# Power-up_delay.net
KiCad netlist of a schematic drawn in Altium Designer
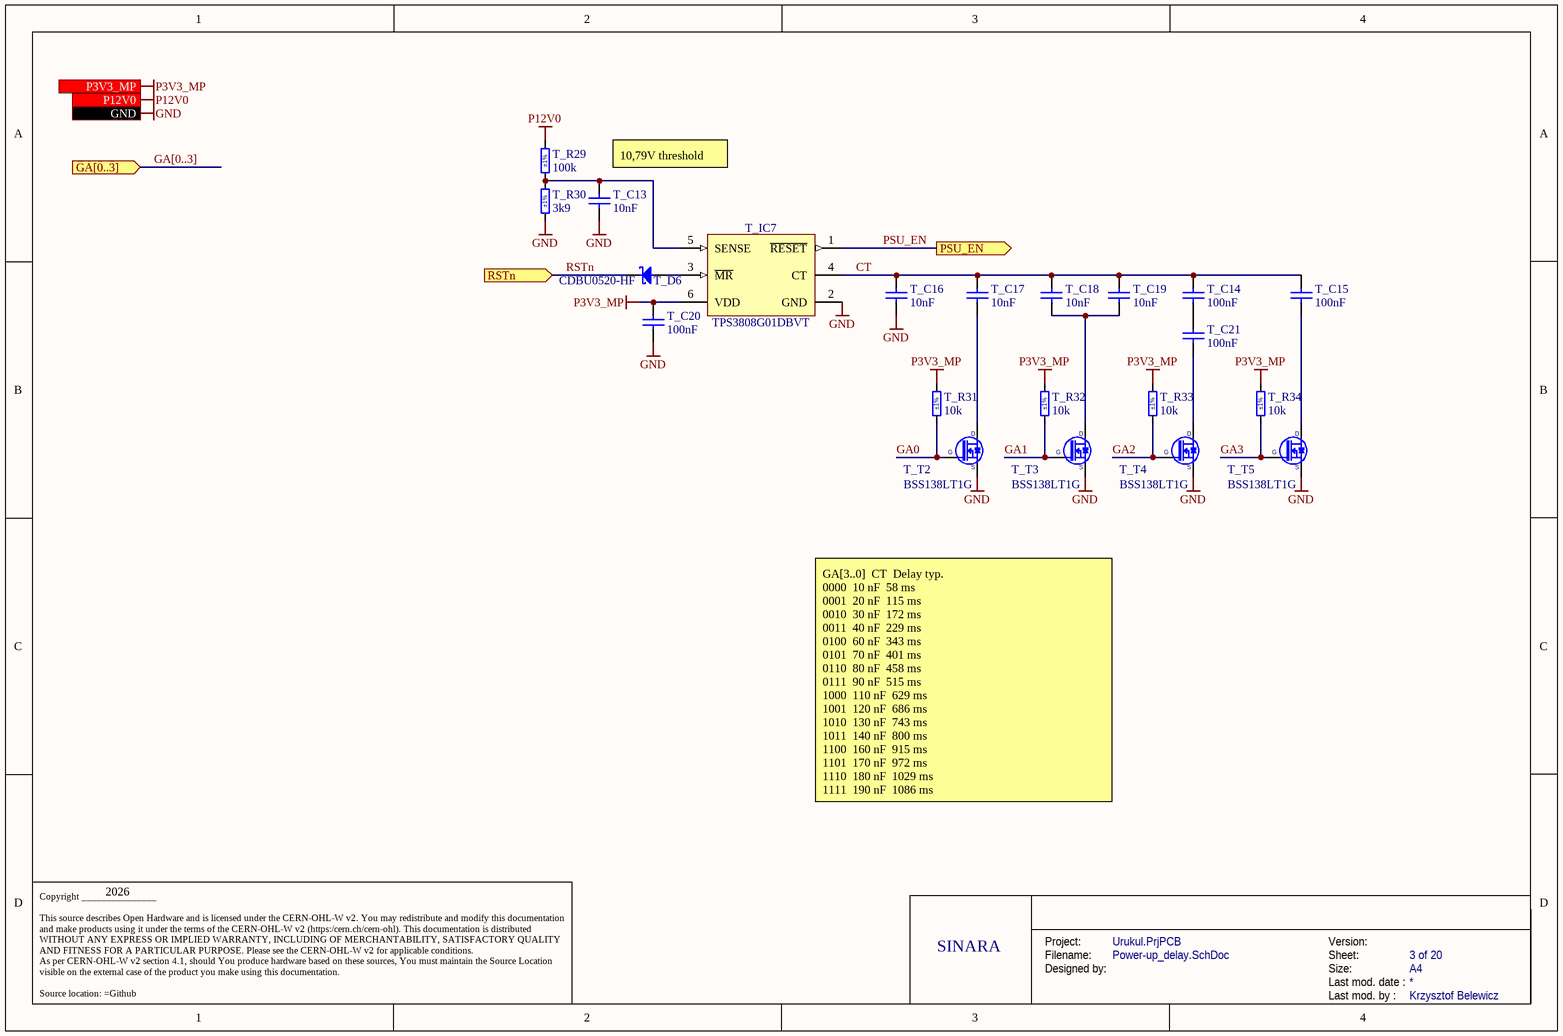
[diagram p0: Power-up_delay.SchDoc]

(export (version "E")
  (design (tool "Eeschema 10.0.6"))
  (components
    (comp (ref "T_C13")
      (value "10nF")
      (footprint "CAPC1005X55N")
      (description "Non-polarised capacitor")
      (fields
        (field (name "PART NUMBER") "CC0402_10NF_16V_10%_X7R")
        (field (name "VOLTAGE") "16V")
        (field (name "AUTHOR") "CERN DEM JLC")
      )
      (libsource (lib "Capacitors") (part "Capacitor - non polarized"))
    )
    (comp (ref "T_C14")
      (value "100nF")
      (footprint "CAPC1005X55N")
      (description "Non-polarised capacitor")
      (fields
        (field (name "PART NUMBER") "CC0402_100NF_16V_10%_X5R")
        (field (name "VOLTAGE") "16V")
        (field (name "AUTHOR") "CERN DEM JLC")
      )
      (libsource (lib "Capacitors") (part "Capacitor - non polarized"))
    )
    (comp (ref "T_C15")
      (value "100nF")
      (footprint "CAPC1005X55N")
      (description "Non-polarised capacitor")
      (fields
        (field (name "PART NUMBER") "CC0402_100NF_16V_10%_X5R")
        (field (name "VOLTAGE") "16V")
        (field (name "AUTHOR") "CERN DEM JLC")
      )
      (libsource (lib "Capacitors") (part "Capacitor - non polarized"))
    )
    (comp (ref "T_C16")
      (value "10nF")
      (footprint "CAPC1005X55N")
      (description "Non-polarised capacitor")
      (fields
        (field (name "PART NUMBER") "CC0402_10NF_16V_10%_X7R")
        (field (name "VOLTAGE") "16V")
        (field (name "AUTHOR") "CERN DEM JLC")
      )
      (libsource (lib "Capacitors") (part "Capacitor - non polarized"))
    )
    (comp (ref "T_C17")
      (value "10nF")
      (footprint "CAPC1005X55N")
      (description "Non-polarised capacitor")
      (fields
        (field (name "PART NUMBER") "CC0402_10NF_16V_10%_X7R")
        (field (name "VOLTAGE") "16V")
        (field (name "AUTHOR") "CERN DEM JLC")
      )
      (libsource (lib "Capacitors") (part "Capacitor - non polarized"))
    )
    (comp (ref "T_C18")
      (value "10nF")
      (footprint "CAPC1005X55N")
      (description "Non-polarised capacitor")
      (fields
        (field (name "PART NUMBER") "CC0402_10NF_16V_10%_X7R")
        (field (name "VOLTAGE") "16V")
        (field (name "AUTHOR") "CERN DEM JLC")
      )
      (libsource (lib "Capacitors") (part "Capacitor - non polarized"))
    )
    (comp (ref "T_C19")
      (value "10nF")
      (footprint "CAPC1005X55N")
      (description "Non-polarised capacitor")
      (fields
        (field (name "PART NUMBER") "CC0402_10NF_16V_10%_X7R")
        (field (name "VOLTAGE") "16V")
        (field (name "AUTHOR") "CERN DEM JLC")
      )
      (libsource (lib "Capacitors") (part "Capacitor - non polarized"))
    )
    (comp (ref "T_C20")
      (value "100nF")
      (footprint "CAPC1005X55N")
      (description "Non-polarised capacitor")
      (fields
        (field (name "PART NUMBER") "CC0402_100NF_16V_10%_X5R")
        (field (name "VOLTAGE") "16V")
        (field (name "AUTHOR") "CERN DEM JLC")
      )
      (libsource (lib "Capacitors") (part "Capacitor - non polarized"))
    )
    (comp (ref "T_C21")
      (value "100nF")
      (footprint "CAPC1005X55N")
      (description "Non-polarised capacitor")
      (fields
        (field (name "PART NUMBER") "CC0402_100NF_16V_10%_X5R")
        (field (name "VOLTAGE") "16V")
        (field (name "AUTHOR") "CERN DEM JLC")
      )
      (libsource (lib "Capacitors") (part "Capacitor - non polarized"))
    )
    (comp (ref "T_D6")
      (value "CDBU0520-HF")
      (footprint "SOD-523F")
      (description "Schottky Diode")
      (fields
        (field (name "VOLTAGE") "20V")
        (field (name "POWER") "500mA")
        (field (name "AUTHOR") "CERN DEM HF")
      )
      (libsource (lib "ICs And Semiconductors") (part "Diode Schottky"))
    )
    (comp (ref "T_IC7")
      (value "TPS3808G01DBVT")
      (footprint "SOT95P280X145-6N")
      (description "Low Quiescent Current, Programmable-Delay Supervisory Circuit")
      (fields
        (field (name "MANUFACTURER") "TEXAS INSTRUMENTS")
        (field (name "MANUFACTURER PART NUMBER") "TPS3808G01DBV")
        (field (name "AUTHOR") "CERN DEM JLC")
      )
      (libsource (lib "ICs And Semiconductors") (part "TPS3808xxxDBV"))
    )
    (comp (ref "T_R29")
      (value "100k")
      (footprint "RESC1005X40N")
      (description "Resistor - 1%")
      (fields
        (field (name "TOLERANCE") "±1%")
        (field (name "PART NUMBER") "R0402_100K_1%_0.0625W_100PPM")
        (field (name "POWER") "0.0625W")
        (field (name "AUTHOR") "CERN DEM JLC")
      )
      (libsource (lib "Resistors") (part "Resistor - 1%"))
    )
    (comp (ref "T_R30")
      (value "3k9")
      (footprint "RESC1005X40N")
      (description "Resistor - 1%")
      (fields
        (field (name "TOLERANCE") "±1%")
        (field (name "PART NUMBER") "R0402_3K9_1%_0.0625W_100PPM")
        (field (name "POWER") "0.0625W")
        (field (name "AUTHOR") "CERN DEM JLC")
      )
      (libsource (lib "Resistors") (part "Resistor - 1%"))
    )
    (comp (ref "T_R31")
      (value "10k")
      (footprint "RESC1005X40N")
      (description "Resistor - 1%")
      (fields
        (field (name "TOLERANCE") "±1%")
        (field (name "PART NUMBER") "R0402_10K_1%_0.0625W_100PPM")
        (field (name "POWER") "0.0625W")
        (field (name "AUTHOR") "CERN DEM JLC")
      )
      (libsource (lib "Resistors") (part "Resistor - 1%"))
    )
    (comp (ref "T_R32")
      (value "10k")
      (footprint "RESC1005X40N")
      (description "Resistor - 1%")
      (fields
        (field (name "TOLERANCE") "±1%")
        (field (name "PART NUMBER") "R0402_10K_1%_0.0625W_100PPM")
        (field (name "POWER") "0.0625W")
        (field (name "AUTHOR") "CERN DEM JLC")
      )
      (libsource (lib "Resistors") (part "Resistor - 1%"))
    )
    (comp (ref "T_R33")
      (value "10k")
      (footprint "RESC1005X40N")
      (description "Resistor - 1%")
      (fields
        (field (name "TOLERANCE") "±1%")
        (field (name "PART NUMBER") "R0402_10K_1%_0.0625W_100PPM")
        (field (name "POWER") "0.0625W")
        (field (name "AUTHOR") "CERN DEM JLC")
      )
      (libsource (lib "Resistors") (part "Resistor - 1%"))
    )
    (comp (ref "T_R34")
      (value "10k")
      (footprint "RESC1005X40N")
      (description "Resistor - 1%")
      (fields
        (field (name "TOLERANCE") "±1%")
        (field (name "PART NUMBER") "R0402_10K_1%_0.0625W_100PPM")
        (field (name "POWER") "0.0625W")
        (field (name "AUTHOR") "CERN DEM JLC")
      )
      (libsource (lib "Resistors") (part "Resistor - 1%"))
    )
    (comp (ref "T_T2")
      (value "BSS138LT1G")
      (footprint "SOT95P240X110-3N")
      (description "N-CHANNEL MOSFET WITH DIODE")
      (fields
        (field (name "MANUFACTURER") "ON SEMICONDUCTOR")
        (field (name "MANUFACTURER PART NUMBER") "BSS138L")
        (field (name "AUTHOR") "CERN DEM JLC")
      )
      (libsource (lib "ICs And Semiconductors") (part "N-MOSFET-D 1G 2S 3D"))
    )
    (comp (ref "T_T3")
      (value "BSS138LT1G")
      (footprint "SOT95P240X110-3N")
      (description "N-CHANNEL MOSFET WITH DIODE")
      (fields
        (field (name "MANUFACTURER") "ON SEMICONDUCTOR")
        (field (name "MANUFACTURER PART NUMBER") "BSS138L")
        (field (name "AUTHOR") "CERN DEM JLC")
      )
      (libsource (lib "ICs And Semiconductors") (part "N-MOSFET-D 1G 2S 3D"))
    )
    (comp (ref "T_T4")
      (value "BSS138LT1G")
      (footprint "SOT95P240X110-3N")
      (description "N-CHANNEL MOSFET WITH DIODE")
      (fields
        (field (name "MANUFACTURER") "ON SEMICONDUCTOR")
        (field (name "MANUFACTURER PART NUMBER") "BSS138L")
        (field (name "AUTHOR") "CERN DEM JLC")
      )
      (libsource (lib "ICs And Semiconductors") (part "N-MOSFET-D 1G 2S 3D"))
    )
    (comp (ref "T_T5")
      (value "BSS138LT1G")
      (footprint "SOT95P240X110-3N")
      (description "N-CHANNEL MOSFET WITH DIODE")
      (fields
        (field (name "MANUFACTURER") "ON SEMICONDUCTOR")
        (field (name "MANUFACTURER PART NUMBER") "BSS138L")
        (field (name "AUTHOR") "CERN DEM JLC")
      )
      (libsource (lib "ICs And Semiconductors") (part "N-MOSFET-D 1G 2S 3D"))
    )
  )
  (nets
    (net (code "1") (name "/CT") (class "Default")
      (node (ref "T_C14") (pin "2") (pinfunction "2_2") (pintype "passive"))
      (node (ref "T_C15") (pin "2") (pinfunction "2_2") (pintype "passive"))
      (node (ref "T_C16") (pin "2") (pinfunction "2_2") (pintype "passive"))
      (node (ref "T_C17") (pin "2") (pinfunction "2_2") (pintype "passive"))
      (node (ref "T_C18") (pin "2") (pinfunction "2_2") (pintype "passive"))
      (node (ref "T_C19") (pin "2") (pinfunction "2_2") (pintype "passive"))
      (node (ref "T_IC7") (pin "4") (pinfunction "CT_4") (pintype "passive"))
    )
    (net (code "2") (name "/GA0") (class "Default")
      (node (ref "T_R31") (pin "1") (pinfunction "1_1") (pintype "passive"))
      (node (ref "T_T2") (pin "1") (pinfunction "G_1") (pintype "passive"))
    )
    (net (code "3") (name "/GA1") (class "Default")
      (node (ref "T_R32") (pin "1") (pinfunction "1_1") (pintype "passive"))
      (node (ref "T_T3") (pin "1") (pinfunction "G_1") (pintype "passive"))
    )
    (net (code "4") (name "/GA2") (class "Default")
      (node (ref "T_R33") (pin "1") (pinfunction "1_1") (pintype "passive"))
      (node (ref "T_T4") (pin "1") (pinfunction "G_1") (pintype "passive"))
    )
    (net (code "5") (name "/GA3") (class "Default")
      (node (ref "T_R34") (pin "1") (pinfunction "1_1") (pintype "passive"))
      (node (ref "T_T5") (pin "1") (pinfunction "G_1") (pintype "passive"))
    )
    (net (code "7") (name "/PSU_EN") (class "Default")
      (node (ref "T_IC7") (pin "1") (pinfunction "~{RESET}_1") (pintype "output"))
    )
    (net (code "8") (name "/RSTn") (class "Default")
      (node (ref "T_D6") (pin "1") (pinfunction "C_1") (pintype "passive"))
    )
    (net (code "9") (name "GND") (class "Default")
      (node (ref "T_C13") (pin "2") (pinfunction "2_2") (pintype "passive"))
      (node (ref "T_C16") (pin "1") (pinfunction "1_1") (pintype "passive"))
      (node (ref "T_C20") (pin "1") (pinfunction "1_1") (pintype "passive"))
      (node (ref "T_IC7") (pin "2") (pinfunction "GND_2") (pintype "power_in"))
      (node (ref "T_R30") (pin "1") (pinfunction "1_1") (pintype "passive"))
      (node (ref "T_T2") (pin "2") (pinfunction "S_2") (pintype "passive"))
      (node (ref "T_T3") (pin "2") (pinfunction "S_2") (pintype "passive"))
      (node (ref "T_T4") (pin "2") (pinfunction "S_2") (pintype "passive"))
      (node (ref "T_T5") (pin "2") (pinfunction "S_2") (pintype "passive"))
    )
    (net (code "10") (name "Net-(T_C14-Pad1)") (class "Default")
      (node (ref "T_C14") (pin "1") (pinfunction "1_1") (pintype "passive"))
      (node (ref "T_C21") (pin "2") (pinfunction "2_2") (pintype "passive"))
    )
    (net (code "11") (name "Net-(T_D6-A)") (class "Default")
      (node (ref "T_D6") (pin "2") (pinfunction "A_2") (pintype "passive"))
      (node (ref "T_IC7") (pin "3") (pinfunction "~{MR}_3") (pintype "input"))
    )
    (net (code "12") (name "Net-(T_IC7-SENSE)") (class "Default")
      (node (ref "T_C13") (pin "1") (pinfunction "1_1") (pintype "passive"))
      (node (ref "T_IC7") (pin "5") (pinfunction "SENSE_5") (pintype "input"))
      (node (ref "T_R29") (pin "2") (pinfunction "2_2") (pintype "passive"))
      (node (ref "T_R30") (pin "2") (pinfunction "2_2") (pintype "passive"))
    )
    (net (code "13") (name "Net-(T_T2-D)") (class "Default")
      (node (ref "T_C17") (pin "1") (pinfunction "1_1") (pintype "passive"))
      (node (ref "T_T2") (pin "3") (pinfunction "D_3") (pintype "passive"))
    )
    (net (code "14") (name "Net-(T_T3-D)") (class "Default")
      (node (ref "T_C18") (pin "1") (pinfunction "1_1") (pintype "passive"))
      (node (ref "T_C19") (pin "1") (pinfunction "1_1") (pintype "passive"))
      (node (ref "T_T3") (pin "3") (pinfunction "D_3") (pintype "passive"))
    )
    (net (code "15") (name "Net-(T_T4-D)") (class "Default")
      (node (ref "T_C21") (pin "1") (pinfunction "1_1") (pintype "passive"))
      (node (ref "T_T4") (pin "3") (pinfunction "D_3") (pintype "passive"))
    )
    (net (code "16") (name "Net-(T_T5-D)") (class "Default")
      (node (ref "T_C15") (pin "1") (pinfunction "1_1") (pintype "passive"))
      (node (ref "T_T5") (pin "3") (pinfunction "D_3") (pintype "passive"))
    )
    (net (code "17") (name "P3V3_MP") (class "Default")
      (node (ref "T_C20") (pin "2") (pinfunction "2_2") (pintype "passive"))
      (node (ref "T_IC7") (pin "6") (pinfunction "VDD_6") (pintype "power_in"))
      (node (ref "T_R31") (pin "2") (pinfunction "2_2") (pintype "passive"))
      (node (ref "T_R32") (pin "2") (pinfunction "2_2") (pintype "passive"))
      (node (ref "T_R33") (pin "2") (pinfunction "2_2") (pintype "passive"))
      (node (ref "T_R34") (pin "2") (pinfunction "2_2") (pintype "passive"))
    )
    (net (code "18") (name "P12V0") (class "Default")
      (node (ref "T_R29") (pin "1") (pinfunction "1_1") (pintype "passive"))
    )
  )
)
